# Arduino_CH32X033F8P6.net
KiCad netlist of a schematic drawn in Altium Designer
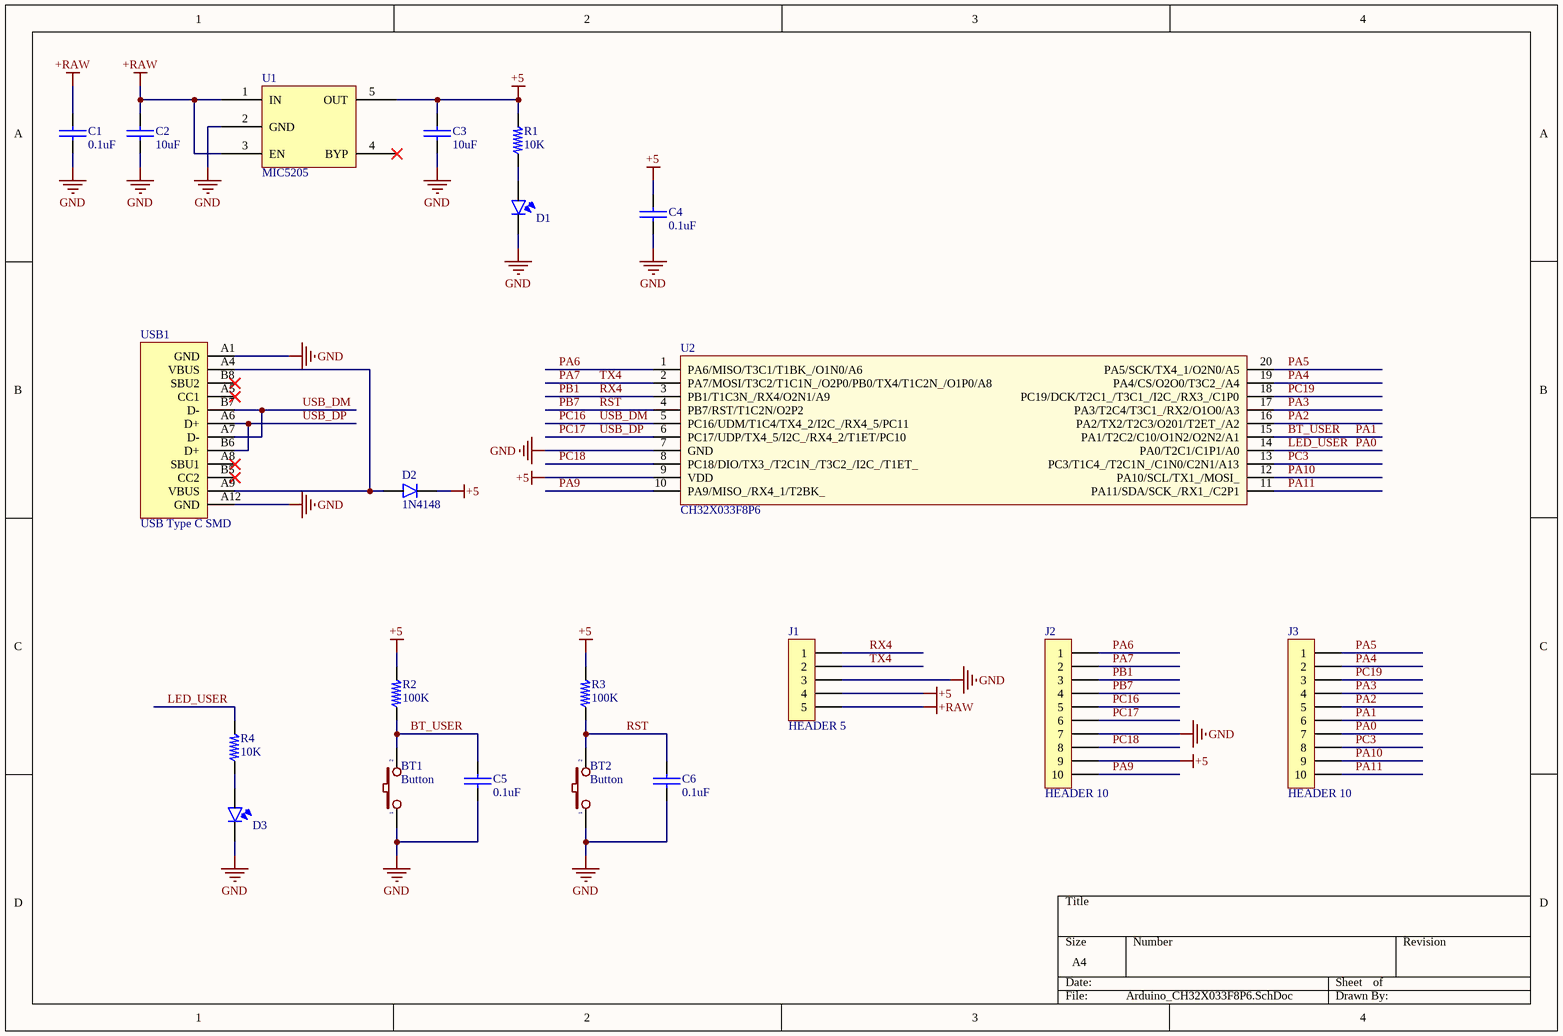
[diagram p0: Arduino_CH32X033F8P6.SchDoc]

(export (version "E")
  (design (tool "Eeschema 10.0.6"))
  (components
    (comp (ref "BT1")
      (value "Button")
      (footprint "Switch 3x4x2mm")
      (libsource (lib "Ho Thanh Phong") (part "Button 2 Pin"))
    )
    (comp (ref "BT2")
      (value "Button")
      (footprint "Switch 3x4x2mm")
      (libsource (lib "Ho Thanh Phong") (part "Button 2 Pin"))
    )
    (comp (ref "C1")
      (value "0.1uF")
      (footprint "CAP 0603")
      (libsource (lib "Ho Thanh Phong") (part "Capacitor SMD"))
    )
    (comp (ref "C2")
      (value "10uF")
      (footprint "CAP 0603")
      (libsource (lib "Ho Thanh Phong") (part "Capacitor SMD"))
    )
    (comp (ref "C3")
      (value "10uF")
      (footprint "CAP 0603")
      (libsource (lib "Ho Thanh Phong") (part "Capacitor SMD"))
    )
    (comp (ref "C4")
      (value "0.1uF")
      (footprint "CAP 0603")
      (libsource (lib "Ho Thanh Phong") (part "Capacitor SMD"))
    )
    (comp (ref "C5")
      (value "0.1uF")
      (footprint "CAP 0603")
      (libsource (lib "Ho Thanh Phong") (part "Capacitor SMD"))
    )
    (comp (ref "C6")
      (value "0.1uF")
      (footprint "CAP 0603")
      (libsource (lib "Ho Thanh Phong") (part "Capacitor SMD"))
    )
    (comp (ref "D1") (value "LED") (footprint "LED 0603") (libsource (lib "Ho Thanh Phong") (part "Led")))
    (comp (ref "D2") (value "1N4148") (footprint "SOD-323") (libsource (lib "Ho Thanh Phong") (part "Diode")))
    (comp (ref "D3") (value "LED") (footprint "LED 0603") (libsource (lib "Ho Thanh Phong") (part "Led")))
    (comp (ref "J1")
      (value "HEADER 5")
      (footprint "HEADER 5")
      (libsource (lib "Ho Thanh Phong") (part "Header 5"))
    )
    (comp (ref "J2")
      (value "HEADER 10")
      (footprint "HEADER 10")
      (libsource (lib "Ho Thanh Phong") (part "Header 10"))
    )
    (comp (ref "J3")
      (value "HEADER 10")
      (footprint "HEADER 10")
      (libsource (lib "Ho Thanh Phong") (part "Header 10"))
    )
    (comp (ref "R1")
      (value "10K")
      (footprint "RES 0603")
      (libsource (lib "Ho Thanh Phong") (part "Resistor SMD"))
    )
    (comp (ref "R2")
      (value "100K")
      (footprint "RES 0603")
      (libsource (lib "Ho Thanh Phong") (part "Resistor SMD"))
    )
    (comp (ref "R3")
      (value "100K")
      (footprint "RES 0603")
      (libsource (lib "Ho Thanh Phong") (part "Resistor SMD"))
    )
    (comp (ref "R4")
      (value "10K")
      (footprint "RES 0603")
      (libsource (lib "Ho Thanh Phong") (part "Resistor SMD"))
    )
    (comp (ref "U1")
      (value "MIC5205")
      (footprint "SOT23-5")
      (description "150mA Low-Noise LDO Regulator")
      (libsource (lib "Ho Thanh Phong") (part "MIC5205"))
    )
    (comp (ref "U2")
      (value "CH32X033F8P6")
      (footprint "TSSOP20_STM")
      (libsource (lib "Ho Thanh Phong") (part "CH32X035/X033"))
    )
    (comp (ref "USB1")
      (value "USB Type C SMD")
      (footprint "USB TYPE C")
      (libsource (lib "Ho Thanh Phong") (part "USB Type C 16"))
    )
  )
  (nets
    (net (code "1") (name "+5") (class "Default")
      (node (ref "C3") (pin "1") (pinfunction "1_1") (pintype "passive"))
      (node (ref "C4") (pin "1") (pinfunction "1_1") (pintype "passive"))
      (node (ref "D2") (pin "2") (pinfunction "2_2") (pintype "passive"))
      (node (ref "J1") (pin "4") (pinfunction "4_4") (pintype "passive"))
      (node (ref "J2") (pin "9") (pinfunction "9_9") (pintype "passive"))
      (node (ref "R1") (pin "2") (pinfunction "2_2") (pintype "passive"))
      (node (ref "R2") (pin "2") (pinfunction "2_2") (pintype "passive"))
      (node (ref "R3") (pin "2") (pinfunction "2_2") (pintype "passive"))
      (node (ref "U1") (pin "5") (pinfunction "OUT_5") (pintype "passive"))
      (node (ref "U2") (pin "9") (pinfunction "VDD_9") (pintype "passive"))
    )
    (net (code "2") (name "+RAW") (class "Default")
      (node (ref "C1") (pin "1") (pinfunction "1_1") (pintype "passive"))
      (node (ref "C2") (pin "1") (pinfunction "1_1") (pintype "passive"))
      (node (ref "J1") (pin "5") (pinfunction "5_5") (pintype "passive"))
      (node (ref "U1") (pin "1") (pinfunction "IN_1") (pintype "passive"))
      (node (ref "U1") (pin "3") (pinfunction "EN_3") (pintype "passive"))
    )
    (net (code "3") (name "/BT_USER") (class "Default")
      (node (ref "BT1") (pin "2") (pinfunction "2_2") (pintype "passive"))
      (node (ref "C5") (pin "1") (pinfunction "1_1") (pintype "passive"))
      (node (ref "J3") (pin "6") (pinfunction "6_6") (pintype "passive"))
      (node (ref "R2") (pin "1") (pinfunction "1_1") (pintype "passive"))
      (node (ref "U2") (pin "15") (pinfunction "PA1/T2C2/C10/O1N2/O2N2/A1_15") (pintype "passive"))
    )
    (net (code "4") (name "/LED_USER") (class "Default")
      (node (ref "J3") (pin "7") (pinfunction "7_7") (pintype "passive"))
      (node (ref "R4") (pin "2") (pinfunction "2_2") (pintype "passive"))
      (node (ref "U2") (pin "14") (pinfunction "PA0/T2C1/C1P1/A0_14") (pintype "passive"))
    )
    (net (code "5") (name "/PA2") (class "Default")
      (node (ref "J3") (pin "5") (pinfunction "5_5") (pintype "passive"))
      (node (ref "U2") (pin "16") (pinfunction "PA2/TX2/T2C3/O201/T2ET_/A2_16") (pintype "passive"))
    )
    (net (code "6") (name "/PA3") (class "Default")
      (node (ref "J3") (pin "4") (pinfunction "4_4") (pintype "passive"))
      (node (ref "U2") (pin "17") (pinfunction "PA3/T2C4/T3C1_/RX2/O1O0/A3_17") (pintype "passive"))
    )
    (net (code "7") (name "/PA4") (class "Default")
      (node (ref "J3") (pin "2") (pinfunction "2_2") (pintype "passive"))
      (node (ref "U2") (pin "19") (pinfunction "PA4/CS/O2O0/T3C2_/A4_19") (pintype "passive"))
    )
    (net (code "8") (name "/PA5") (class "Default")
      (node (ref "J3") (pin "1") (pinfunction "1_1") (pintype "passive"))
      (node (ref "U2") (pin "20") (pinfunction "PA5/SCK/TX4_1/O2N0/A5_20") (pintype "passive"))
    )
    (net (code "9") (name "/PA6") (class "Default")
      (node (ref "J2") (pin "1") (pinfunction "1_1") (pintype "passive"))
      (node (ref "U2") (pin "1") (pinfunction "PA6/MISO/T3C1/T1BK_/O1N0/A6_1") (pintype "passive"))
    )
    (net (code "10") (name "/PA7") (class "Default")
      (node (ref "J1") (pin "2") (pinfunction "2_2") (pintype "passive"))
      (node (ref "J2") (pin "2") (pinfunction "2_2") (pintype "passive"))
      (node (ref "U2") (pin "2") (pinfunction "PA7/MOSI/T3C2/T1C1N_/O2P0/PB0/TX4/T1C2N_/O1P0/A8_2") (pintype "passive"))
    )
    (net (code "11") (name "/PA9") (class "Default")
      (node (ref "J2") (pin "10") (pinfunction "10_10") (pintype "passive"))
      (node (ref "U2") (pin "10") (pinfunction "PA9/MISO_/RX4_1/T2BK__10") (pintype "passive"))
    )
    (net (code "12") (name "/PA10") (class "Default")
      (node (ref "J3") (pin "9") (pinfunction "9_9") (pintype "passive"))
      (node (ref "U2") (pin "12") (pinfunction "PA10/SCL/TX1_/MOSI__12") (pintype "passive"))
    )
    (net (code "13") (name "/PA11") (class "Default")
      (node (ref "J3") (pin "10") (pinfunction "10_10") (pintype "passive"))
      (node (ref "U2") (pin "11") (pinfunction "PA11/SDA/SCK_/RX1_/C2P1_11") (pintype "passive"))
    )
    (net (code "14") (name "/PB1") (class "Default")
      (node (ref "J1") (pin "1") (pinfunction "1_1") (pintype "passive"))
      (node (ref "J2") (pin "3") (pinfunction "3_3") (pintype "passive"))
      (node (ref "U2") (pin "3") (pinfunction "PB1/T1C3N_/RX4/O2N1/A9_3") (pintype "passive"))
    )
    (net (code "15") (name "/PB7") (class "Default")
      (node (ref "BT2") (pin "2") (pinfunction "2_2") (pintype "passive"))
      (node (ref "C6") (pin "1") (pinfunction "1_1") (pintype "passive"))
      (node (ref "J2") (pin "4") (pinfunction "4_4") (pintype "passive"))
      (node (ref "R3") (pin "1") (pinfunction "1_1") (pintype "passive"))
      (node (ref "U2") (pin "4") (pinfunction "PB7/RST/T1C2N/O2P2_4") (pintype "passive"))
    )
    (net (code "16") (name "/PC3") (class "Default")
      (node (ref "J3") (pin "8") (pinfunction "8_8") (pintype "passive"))
      (node (ref "U2") (pin "13") (pinfunction "PC3/T1C4_/T2C1N_/C1N0/C2N1/A13_13") (pintype "passive"))
    )
    (net (code "17") (name "/PC16") (class "Default")
      (node (ref "J2") (pin "5") (pinfunction "5_5") (pintype "passive"))
      (node (ref "U2") (pin "5") (pinfunction "PC16/UDM/T1C4/TX4_2/I2C_/RX4_5/PC11_5") (pintype "passive"))
      (node (ref "USB1") (pin "A7") (pinfunction "D-_A7") (pintype "passive"))
      (node (ref "USB1") (pin "B7") (pinfunction "D-_B7") (pintype "passive"))
    )
    (net (code "18") (name "/PC17") (class "Default")
      (node (ref "J2") (pin "6") (pinfunction "6_6") (pintype "passive"))
      (node (ref "U2") (pin "6") (pinfunction "PC17/UDP/TX4_5/I2C_/RX4_2/T1ET/PC10_6") (pintype "passive"))
      (node (ref "USB1") (pin "A6") (pinfunction "D+_A6") (pintype "passive"))
      (node (ref "USB1") (pin "B6") (pinfunction "D+_B6") (pintype "passive"))
    )
    (net (code "19") (name "/PC18") (class "Default")
      (node (ref "J2") (pin "8") (pinfunction "8_8") (pintype "passive"))
      (node (ref "U2") (pin "8") (pinfunction "PC18/DIO/TX3_/T2C1N_/T3C2_/I2C_/T1ET__8") (pintype "passive"))
    )
    (net (code "20") (name "/PC19") (class "Default")
      (node (ref "J3") (pin "3") (pinfunction "3_3") (pintype "passive"))
      (node (ref "U2") (pin "18") (pinfunction "PC19/DCK/T2C1_/T3C1_/I2C_/RX3_/C1P0_18") (pintype "passive"))
    )
    (net (code "21") (name "GND") (class "Default")
      (node (ref "BT1") (pin "1") (pinfunction "1_1") (pintype "passive"))
      (node (ref "BT2") (pin "1") (pinfunction "1_1") (pintype "passive"))
      (node (ref "C1") (pin "2") (pinfunction "2_2") (pintype "passive"))
      (node (ref "C2") (pin "2") (pinfunction "2_2") (pintype "passive"))
      (node (ref "C3") (pin "2") (pinfunction "2_2") (pintype "passive"))
      (node (ref "C4") (pin "2") (pinfunction "2_2") (pintype "passive"))
      (node (ref "C5") (pin "2") (pinfunction "2_2") (pintype "passive"))
      (node (ref "C6") (pin "2") (pinfunction "2_2") (pintype "passive"))
      (node (ref "D1") (pin "2") (pinfunction "2_2") (pintype "passive"))
      (node (ref "D3") (pin "2") (pinfunction "2_2") (pintype "passive"))
      (node (ref "J1") (pin "3") (pinfunction "3_3") (pintype "passive"))
      (node (ref "J2") (pin "7") (pinfunction "7_7") (pintype "passive"))
      (node (ref "U1") (pin "2") (pinfunction "GND_2") (pintype "passive"))
      (node (ref "U2") (pin "7") (pinfunction "GND_7") (pintype "passive"))
      (node (ref "USB1") (pin "A1") (pinfunction "GND_A1") (pintype "passive"))
      (node (ref "USB1") (pin "A12") (pinfunction "GND_A12") (pintype "passive"))
    )
    (net (code "22") (name "Net-(D1-Pad1)") (class "Default")
      (node (ref "D1") (pin "1") (pinfunction "1_1") (pintype "passive"))
      (node (ref "R1") (pin "1") (pinfunction "1_1") (pintype "passive"))
    )
    (net (code "23") (name "Net-(D2-Pad1)") (class "Default")
      (node (ref "D2") (pin "1") (pinfunction "1_1") (pintype "passive"))
      (node (ref "USB1") (pin "A4") (pinfunction "VBUS_A4") (pintype "passive"))
      (node (ref "USB1") (pin "A9") (pinfunction "VBUS_A9") (pintype "passive"))
    )
    (net (code "24") (name "Net-(D3-Pad1)") (class "Default")
      (node (ref "D3") (pin "1") (pinfunction "1_1") (pintype "passive"))
      (node (ref "R4") (pin "1") (pinfunction "1_1") (pintype "passive"))
    )
    (net (code "25") (name "unconnected-(U1-BYP-Pad4)") (class "Default")
      (node (ref "U1") (pin "4") (pinfunction "BYP_4") (pintype "passive+no_connect"))
    )
    (net (code "26") (name "unconnected-(USB1-CC1-PadA5)") (class "Default")
      (node (ref "USB1") (pin "A5") (pinfunction "CC1_A5") (pintype "passive+no_connect"))
    )
    (net (code "27") (name "unconnected-(USB1-CC2-PadB5)") (class "Default")
      (node (ref "USB1") (pin "B5") (pinfunction "CC2_B5") (pintype "passive+no_connect"))
    )
    (net (code "28") (name "unconnected-(USB1-SBU1-PadA8)") (class "Default")
      (node (ref "USB1") (pin "A8") (pinfunction "SBU1_A8") (pintype "passive+no_connect"))
    )
    (net (code "29") (name "unconnected-(USB1-SBU2-PadB8)") (class "Default")
      (node (ref "USB1") (pin "B8") (pinfunction "SBU2_B8") (pintype "passive+no_connect"))
    )
  )
)
